# 4_-_EthernetPHY.net
KiCad netlist of a schematic drawn in Altium Designer
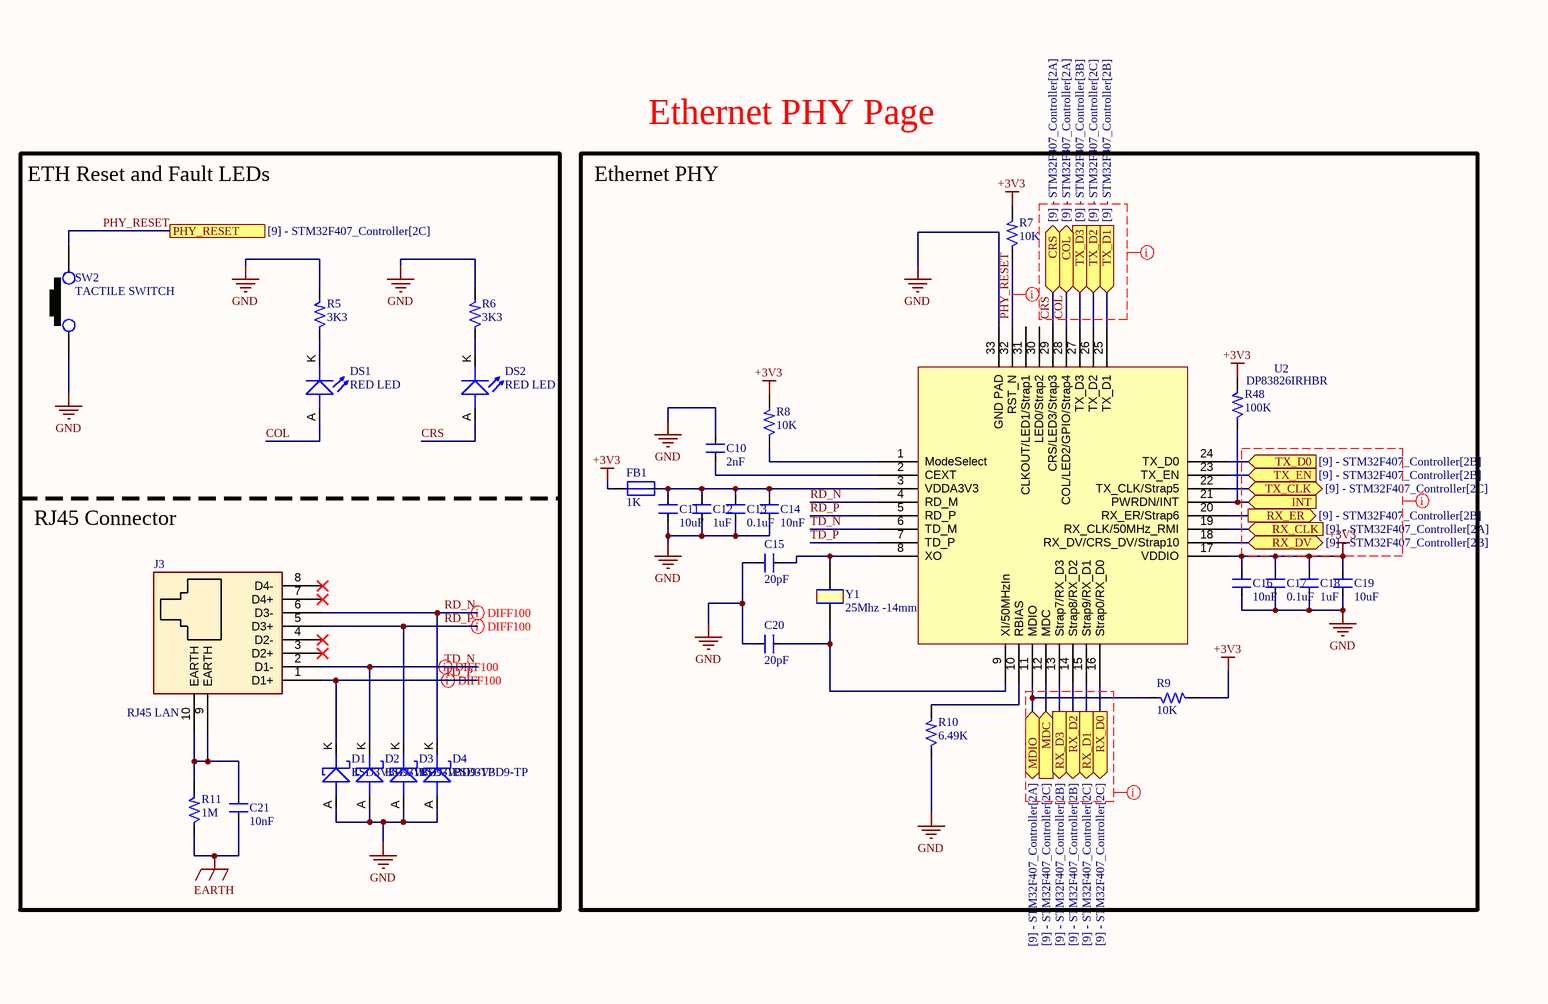
[diagram p0: [4] - EthernetPHY.SchDoc]

(export (version "E")
  (design (tool "Eeschema 10.0.6"))
  (components
    (comp (ref "C10")
      (value "2nF")
      (footprint "CAP_0805")
      (description "2000pF ±10% 50V Ceramic Capacitor X7R 0805 (2012 Metric)")
      (fields
        (field (name "MANUFACTURER") "Samsung Electro-Mechanics")
        (field (name "MANUFACTURER PART NUMBER") "CL21B202KBANNNC")
      )
      (libsource (lib "ESTEEMPCBLIB") (part "CAP_2nF-50V-10%-0805"))
    )
    (comp (ref "C11")
      (value "10uF")
      (footprint "CAP_1206")
      (description "10µF ±10% 50V Ceramic Capacitor X7R 1206 (3216 Metric)")
      (fields
        (field (name "MANUFACTURER") "KEMET")
        (field (name "MANUFACTURER PART NUMBER") "CL31B106KBHNNNE")
      )
      (libsource (lib "ESTEEMPCBLIB") (part "CAP_10uF-50V-10%-1206"))
    )
    (comp (ref "C12")
      (value "1uF")
      (footprint "CAP_0805")
      (description "1µF ±5% 50V Ceramic Capacitor X7R 0805 (2012 Metric)")
      (fields
        (field (name "MANUFACTURER") "Samsung")
        (field (name "MANUFACTURER PART NUMBER") "CC0805JKX7R9BB105")
      )
      (libsource (lib "ESTEEMPCBLIB") (part "CAP_1uF-50V-5%-0805"))
    )
    (comp (ref "C13")
      (value "0.1uF")
      (footprint "CAP_0805")
      (description "0.1µF ±5% 50V Ceramic Capacitor X7R 0805 (2012 Metric)")
      (fields
        (field (name "MANUFACTURER") "AVX Corporation")
        (field (name "MANUFACTURER PART NUMBER") "08055C104JAT4A")
      )
      (libsource (lib "ESTEEMPCBLIB") (part "CAP_0.1uF-50V-5%-0805"))
    )
    (comp (ref "C14")
      (value "10nF")
      (footprint "CAP_0805")
      (description "10000pF ±10% 50V Ceramic Capacitor X7R 0805 (2012 Metric)")
      (fields
        (field (name "MANUFACTURER") "Samsung")
        (field (name "MANUFACTURER PART NUMBER") "C0805C103K5RECAUTO")
      )
      (libsource (lib "ESTEEMPCBLIB") (part "CAP_10nF-50V-10%-0805"))
    )
    (comp (ref "C15")
      (value "20pF")
      (footprint "CAP_0805")
      (description "±10% 50V Ceramic Capacitor C0G, NP0 0805 (2012 Metric)")
      (fields
        (field (name "MANUFACTURER") "AVX Corporation")
        (field (name "MANUFACTURER PART NUMBER") "08055A200KAT2A")
      )
      (libsource (lib "ESTEEMPCBLIB") (part "CAP_20pF-50V-10%-0805"))
    )
    (comp (ref "C16")
      (value "10nF")
      (footprint "CAP_0805")
      (description "10000pF ±10% 50V Ceramic Capacitor X7R 0805 (2012 Metric)")
      (fields
        (field (name "MANUFACTURER") "Samsung")
        (field (name "MANUFACTURER PART NUMBER") "C0805C103K5RECAUTO")
      )
      (libsource (lib "ESTEEMPCBLIB") (part "CAP_10nF-50V-10%-0805"))
    )
    (comp (ref "C17")
      (value "0.1uF")
      (footprint "CAP_0805")
      (description "0.1µF ±5% 50V Ceramic Capacitor X7R 0805 (2012 Metric)")
      (fields
        (field (name "MANUFACTURER") "AVX Corporation")
        (field (name "MANUFACTURER PART NUMBER") "08055C104JAT4A")
      )
      (libsource (lib "ESTEEMPCBLIB") (part "CAP_0.1uF-50V-5%-0805"))
    )
    (comp (ref "C18")
      (value "1uF")
      (footprint "CAP_0805")
      (description "1µF ±5% 50V Ceramic Capacitor X7R 0805 (2012 Metric)")
      (fields
        (field (name "MANUFACTURER") "Samsung")
        (field (name "MANUFACTURER PART NUMBER") "CC0805JKX7R9BB105")
      )
      (libsource (lib "ESTEEMPCBLIB") (part "CAP_1uF-50V-5%-0805"))
    )
    (comp (ref "C19")
      (value "10uF")
      (footprint "CAP_1206")
      (description "10µF ±10% 50V Ceramic Capacitor X7R 1206 (3216 Metric)")
      (fields
        (field (name "MANUFACTURER") "KEMET")
        (field (name "MANUFACTURER PART NUMBER") "CL31B106KBHNNNE")
      )
      (libsource (lib "ESTEEMPCBLIB") (part "CAP_10uF-50V-10%-1206"))
    )
    (comp (ref "C20")
      (value "20pF")
      (footprint "CAP_0805")
      (description "±10% 50V Ceramic Capacitor C0G, NP0 0805 (2012 Metric)")
      (fields
        (field (name "MANUFACTURER") "AVX Corporation")
        (field (name "MANUFACTURER PART NUMBER") "08055A200KAT2A")
      )
      (libsource (lib "ESTEEMPCBLIB") (part "CAP_20pF-50V-10%-0805"))
    )
    (comp (ref "C21")
      (value "10nF")
      (footprint "CAP_P196_102X287_H332_RAD_TH")
      (description "10000pF ±10% 1000V (1kV) Ceramic Capacitor X7R Radial")
      (fields
        (field (name "MANUFACTURER") "Yageo")
        (field (name "MANUFACTURER PART NUMBER") "RDER73A103K2K1H03B")
      )
      (libsource (lib "ESTEEMPCBLIB") (part "CAP_10nF-1KV-10%-RAD-TH"))
    )
    (comp (ref "D1")
      (value "ESD3V3D9-TP")
      (footprint "DIO_SOD-923")
      (description "TVS DIODE 3.3V 8.8V SOD923")
      (fields (field (name "MANUFACTURER") "Micro Commercial Co"))
      (libsource (lib "ESTEEMPCBLIB") (part "DIO-T_3.3V-8.8V-10A-SOD923"))
    )
    (comp (ref "D2")
      (value "ESD3V3D9-TP")
      (footprint "DIO_SOD-923")
      (description "TVS DIODE 3.3V 8.8V SOD923")
      (fields (field (name "MANUFACTURER") "Micro Commercial Co"))
      (libsource (lib "ESTEEMPCBLIB") (part "DIO-T_3.3V-8.8V-10A-SOD923"))
    )
    (comp (ref "D3")
      (value "ESD3V3D9-TP")
      (footprint "DIO_SOD-923")
      (description "TVS DIODE 3.3V 8.8V SOD923")
      (fields (field (name "MANUFACTURER") "Micro Commercial Co"))
      (libsource (lib "ESTEEMPCBLIB") (part "DIO-T_3.3V-8.8V-10A-SOD923"))
    )
    (comp (ref "D4")
      (value "ESD3V3D9-TP")
      (footprint "DIO_SOD-923")
      (description "TVS DIODE 3.3V 8.8V SOD923")
      (fields (field (name "MANUFACTURER") "Micro Commercial Co"))
      (libsource (lib "ESTEEMPCBLIB") (part "DIO-T_3.3V-8.8V-10A-SOD923"))
    )
    (comp (ref "DS1")
      (value "RED LED")
      (footprint "LED_0805")
      (description "Red 631nm LED Indication - Discrete 2V 0805 (2012 Metric)")
      (fields
        (field (name "MANUFACTURER") "Vishay Lite-On")
        (field (name "MANUFACTURER PART NUMBER") "LTST-C171KRKT")
      )
      (libsource (lib "ESTEEMPCBLIB") (part "LED_RED-2V-20mA-0805"))
    )
    (comp (ref "DS2")
      (value "RED LED")
      (footprint "LED_0805")
      (description "Red 631nm LED Indication - Discrete 2V 0805 (2012 Metric)")
      (fields
        (field (name "MANUFACTURER") "Vishay Lite-On")
        (field (name "MANUFACTURER PART NUMBER") "LTST-C171KRKT")
      )
      (libsource (lib "ESTEEMPCBLIB") (part "LED_RED-2V-20mA-0805"))
    )
    (comp (ref "FB1")
      (value "1K")
      (footprint "IND_0805")
      (description "1 kOhms @ 100MHz 1 Power Line Ferrite Bead 0805 (2012 Metric) 1.6A")
      (fields
        (field (name "MANUFACTURER") "Laird")
        (field (name "MANUFACTURER PART NUMBER") "BLM21SP102SH1D")
      )
      (libsource (lib "ESTEEMPCBLIB") (part "FB_1K-100MHZ-1.6A-0805"))
    )
    (comp (ref "J3")
      (value "RJ45 LAN")
      (footprint "CON10_P106_RJ45_TH_ST")
      (description "8 Pins, 2 Row 2.54mm Pitch, right angle Connector, male")
      (fields
        (field (name "MANUFACTURER") "Assmann")
        (field (name "MANUFACTURER PART NUMBER") "A-2004-2-4-LPS-N-R")
      )
      (libsource (lib "ESTEEMPCBLIB") (part "CON-SKT-RJ_8C8P-RA-TH"))
    )
    (comp (ref "R5")
      (value "3K3")
      (footprint "RES_0603")
      (description "3.3 kOhms ±1% 0.1W, 1/10W Chip Resistor 0603 (1608 Metric) Automotive AEC-Q200 Thick Film")
      (fields (field (name "MANUFACTURER") "Wilson") (field (name "MANUFACTURER PART NUMBER") "WR06X3301FTL"))
      (libsource (lib "ESTEEMPCBLIB") (part "RES_3.3K-0.1W-1%-0603"))
    )
    (comp (ref "R6")
      (value "3K3")
      (footprint "RES_0603")
      (description "3.3 kOhms ±1% 0.1W, 1/10W Chip Resistor 0603 (1608 Metric) Automotive AEC-Q200 Thick Film")
      (fields (field (name "MANUFACTURER") "Wilson") (field (name "MANUFACTURER PART NUMBER") "WR06X3301FTL"))
      (libsource (lib "ESTEEMPCBLIB") (part "RES_3.3K-0.1W-1%-0603"))
    )
    (comp (ref "R7")
      (value "10K")
      (footprint "RES_0603")
      (description "10 kOhms ±1% 0.1W, 1/10W Chip Resistor 0603 (1608 Metric) Automotive AEC-Q200 Thick Film")
      (fields (field (name "MANUFACTURER") "Walsin") (field (name "MANUFACTURER PART NUMBER") "WR06X1002FTL"))
      (libsource (lib "ESTEEMPCBLIB") (part "RES_10K-0.1W-1%-0603"))
    )
    (comp (ref "R8")
      (value "10K")
      (footprint "RES_0603")
      (description "10 kOhms ±1% 0.1W, 1/10W Chip Resistor 0603 (1608 Metric) Automotive AEC-Q200 Thick Film")
      (fields (field (name "MANUFACTURER") "Walsin") (field (name "MANUFACTURER PART NUMBER") "WR06X1002FTL"))
      (libsource (lib "ESTEEMPCBLIB") (part "RES_10K-0.1W-1%-0603"))
    )
    (comp (ref "R9")
      (value "10K")
      (footprint "RES_0603")
      (description "10 kOhms ±1% 0.1W, 1/10W Chip Resistor 0603 (1608 Metric) Automotive AEC-Q200 Thick Film")
      (fields (field (name "MANUFACTURER") "Walsin") (field (name "MANUFACTURER PART NUMBER") "WR06X1002FTL"))
      (libsource (lib "ESTEEMPCBLIB") (part "RES_10K-0.1W-1%-0603"))
    )
    (comp (ref "R10")
      (value "6.49K")
      (footprint "RES_0805")
      (description "6.49 kOhms ±1% 0.125W, 1/8W Chip Resistor 0805 (2012 Metric) Moisture Resistant Thick Film")
      (fields
        (field (name "MANUFACTURER") "Stackpole Electronics")
        (field (name "MANUFACTURER PART NUMBER") "RC0805FR-076K49L")
      )
      (libsource (lib "ESTEEMPCBLIB") (part "RES_6.49K-0.125W-1%-0805"))
    )
    (comp (ref "R11")
      (value "1M")
      (footprint "RES_1206")
      (fields (field (name "MANUFACTURER") "Walsin") (field (name "MANUFACTURER PART NUMBER") "WR12X1004FTL"))
      (libsource (lib "ESTEEMPCBLIB") (part "RES_1M-0.25W-1%-1206"))
    )
    (comp (ref "R48")
      (value "100K")
      (footprint "RES_0603")
      (description "100 kOhms ±1% 0.1W, 1/10W Chip Resistor 0603 (1608 Metric) Automotive AEC-Q200 Thick Film")
      (fields
        (field (name "MANUFACTURER") "Stackpole Electronics")
        (field (name "MANUFACTURER PART NUMBER") "RMCF0603FT100K")
      )
      (libsource (lib "ESTEEMPCBLIB") (part "RES_100K-0.1W-1%-0603"))
    )
    (comp (ref "SW2")
      (value "TACTILE SWITCH")
      (footprint "SW_342_SMD")
      (description "Tactile Switch SPST-NO Top Actuated Surface Mount")
      (fields
        (field (name "MANUFACTURER") "ITT C&K")
        (field (name "MANUFACTURER PART NUMBER") "RS-282G05A3-SMRT")
      )
      (libsource (lib "ESTEEMPCBLIB") (part "SW1_RS-282G05A3-SMRT-SMD"))
    )
    (comp (ref "U2")
      (value "DP83826IRHBR")
      (footprint "VQFN32_19_218_23X9_SMD")
      (fields (field (name "MANUFACTURER") "Texas Instruments"))
      (libsource (lib "ESTEEMPCBLIB") (part "IC_DP83826IRHBR"))
    )
    (comp (ref "Y1")
      (value "25Mhz -14mm")
      (footprint "XTAL_314_240X47_SMD")
      (description "25MHz ±30ppm Crystal 20pF 30 Ohms HC-49/US")
      (fields
        (field (name "MANUFACTURER") "Abracon")
        (field (name "MANUFACTURER PART NUMBER") "FOXSDLF/250F-20")
      )
      (libsource (lib "ESTEEMPCBLIB") (part "XTAL_25Mhz-FOXSDLF/250F-20"))
    )
  )
  (nets
    (net (code "1") (name "+3V3") (class "Default")
      (node (ref "C16") (pin "1") (pinfunction "1_1") (pintype "passive"))
      (node (ref "C17") (pin "2") (pinfunction "2_2") (pintype "passive"))
      (node (ref "C18") (pin "1") (pinfunction "1_1") (pintype "passive"))
      (node (ref "C19") (pin "2") (pinfunction "2_2") (pintype "passive"))
      (node (ref "FB1") (pin "1") (pinfunction "1_1") (pintype "passive"))
      (node (ref "R48") (pin "2") (pinfunction "2_2") (pintype "passive"))
      (node (ref "R7") (pin "2") (pinfunction "2_2") (pintype "passive"))
      (node (ref "R8") (pin "2") (pinfunction "2_2") (pintype "passive"))
      (node (ref "R9") (pin "2") (pinfunction "2_2") (pintype "passive"))
      (node (ref "U2") (pin "17") (pinfunction "VDDIO_17") (pintype "passive"))
    )
    (net (code "2") (name "/COL") (class "Default")
      (node (ref "DS1") (pin "A") (pinfunction "ANODE_A") (pintype "passive"))
      (node (ref "U2") (pin "28") (pinfunction "COL/LED2/GPIO/Strap4_28") (pintype "passive"))
    )
    (net (code "3") (name "/CRS") (class "Default")
      (node (ref "DS2") (pin "A") (pinfunction "ANODE_A") (pintype "passive"))
      (node (ref "U2") (pin "29") (pinfunction "CRS/LED3/Strap3_29") (pintype "passive"))
    )
    (net (code "4") (name "/INT") (class "Default")
      (node (ref "R48") (pin "1") (pinfunction "1_1") (pintype "passive"))
      (node (ref "U2") (pin "21") (pinfunction "PWRDN/INT_21") (pintype "passive"))
    )
    (net (code "5") (name "/MDC") (class "Default")
      (node (ref "U2") (pin "12") (pinfunction "MDC_12") (pintype "passive"))
    )
    (net (code "6") (name "/MDIO") (class "Default")
      (node (ref "R9") (pin "1") (pinfunction "1_1") (pintype "passive"))
      (node (ref "U2") (pin "11") (pinfunction "MDIO_11") (pintype "passive"))
    )
    (net (code "7") (name "/PHY_RESET") (class "Default")
      (node (ref "R7") (pin "1") (pinfunction "1_1") (pintype "passive"))
      (node (ref "SW2") (pin "2") (pinfunction "2_2") (pintype "passive"))
      (node (ref "U2") (pin "32") (pinfunction "RST_N_32") (pintype "passive"))
    )
    (net (code "8") (name "/RD_N") (class "Default")
      (node (ref "D4") (pin "K") (pinfunction "K_K") (pintype "passive"))
      (node (ref "J3") (pin "6") (pinfunction "D3-_6") (pintype "passive"))
      (node (ref "U2") (pin "4") (pinfunction "RD_M_4") (pintype "passive"))
    )
    (net (code "9") (name "/RD_P") (class "Default")
      (node (ref "D3") (pin "K") (pinfunction "K_K") (pintype "passive"))
      (node (ref "J3") (pin "5") (pinfunction "D3+_5") (pintype "passive"))
      (node (ref "U2") (pin "5") (pinfunction "RD_P_5") (pintype "passive"))
    )
    (net (code "10") (name "/RX_CLK") (class "Default")
      (node (ref "U2") (pin "19") (pinfunction "RX_CLK/50MHz_RMI_19") (pintype "passive"))
    )
    (net (code "11") (name "/RX_D0") (class "Default")
      (node (ref "U2") (pin "16") (pinfunction "Strap0/RX_D0_16") (pintype "passive"))
    )
    (net (code "12") (name "/RX_D1") (class "Default")
      (node (ref "U2") (pin "15") (pinfunction "Strap9/RX_D1_15") (pintype "passive"))
    )
    (net (code "13") (name "/RX_D2") (class "Default")
      (node (ref "U2") (pin "14") (pinfunction "Strap8/RX_D2_14") (pintype "passive"))
    )
    (net (code "14") (name "/RX_D3") (class "Default")
      (node (ref "U2") (pin "13") (pinfunction "Strap7/RX_D3_13") (pintype "passive"))
    )
    (net (code "15") (name "/RX_DV") (class "Default")
      (node (ref "U2") (pin "18") (pinfunction "RX_DV/CRS_DV/Strap10_18") (pintype "passive"))
    )
    (net (code "16") (name "/RX_ER") (class "Default")
      (node (ref "U2") (pin "20") (pinfunction "RX_ER/Strap6_20") (pintype "passive"))
    )
    (net (code "17") (name "/TD_N") (class "Default")
      (node (ref "D2") (pin "K") (pinfunction "K_K") (pintype "passive"))
      (node (ref "J3") (pin "2") (pinfunction "D1-_2") (pintype "passive"))
      (node (ref "U2") (pin "6") (pinfunction "TD_M_6") (pintype "passive"))
    )
    (net (code "18") (name "/TD_P") (class "Default")
      (node (ref "D1") (pin "K") (pinfunction "K_K") (pintype "passive"))
      (node (ref "J3") (pin "1") (pinfunction "D1+_1") (pintype "passive"))
      (node (ref "U2") (pin "7") (pinfunction "TD_P_7") (pintype "passive"))
    )
    (net (code "19") (name "/TX_CLK") (class "Default")
      (node (ref "U2") (pin "22") (pinfunction "TX_CLK/Strap5_22") (pintype "passive"))
    )
    (net (code "20") (name "/TX_D0") (class "Default")
      (node (ref "U2") (pin "24") (pinfunction "TX_D0_24") (pintype "passive"))
    )
    (net (code "21") (name "/TX_D1") (class "Default")
      (node (ref "U2") (pin "25") (pinfunction "TX_D1_25") (pintype "passive"))
    )
    (net (code "22") (name "/TX_D2") (class "Default")
      (node (ref "U2") (pin "26") (pinfunction "TX_D2_26") (pintype "passive"))
    )
    (net (code "23") (name "/TX_D3") (class "Default")
      (node (ref "U2") (pin "27") (pinfunction "TX_D3_27") (pintype "passive"))
    )
    (net (code "24") (name "/TX_EN") (class "Default")
      (node (ref "U2") (pin "23") (pinfunction "TX_EN_23") (pintype "passive"))
    )
    (net (code "25") (name "EARTH") (class "Default")
      (node (ref "C21") (pin "1") (pinfunction "1_1") (pintype "passive"))
      (node (ref "R11") (pin "1") (pinfunction "1_1") (pintype "passive"))
    )
    (net (code "26") (name "GND") (class "Default")
      (node (ref "C10") (pin "1") (pinfunction "1_1") (pintype "passive"))
      (node (ref "C11") (pin "1") (pinfunction "1_1") (pintype "passive"))
      (node (ref "C12") (pin "1") (pinfunction "1_1") (pintype "passive"))
      (node (ref "C13") (pin "2") (pinfunction "2_2") (pintype "passive"))
      (node (ref "C14") (pin "1") (pinfunction "1_1") (pintype "passive"))
      (node (ref "C15") (pin "1") (pinfunction "1_1") (pintype "passive"))
      (node (ref "C16") (pin "2") (pinfunction "2_2") (pintype "passive"))
      (node (ref "C17") (pin "1") (pinfunction "1_1") (pintype "passive"))
      (node (ref "C18") (pin "2") (pinfunction "2_2") (pintype "passive"))
      (node (ref "C19") (pin "1") (pinfunction "1_1") (pintype "passive"))
      (node (ref "C20") (pin "1") (pinfunction "1_1") (pintype "passive"))
      (node (ref "D1") (pin "A") (pinfunction "A_A") (pintype "passive"))
      (node (ref "D2") (pin "A") (pinfunction "A_A") (pintype "passive"))
      (node (ref "D3") (pin "A") (pinfunction "A_A") (pintype "passive"))
      (node (ref "D4") (pin "A") (pinfunction "A_A") (pintype "passive"))
      (node (ref "R10") (pin "1") (pinfunction "1_1") (pintype "passive"))
      (node (ref "R5") (pin "2") (pinfunction "2_2") (pintype "passive"))
      (node (ref "R6") (pin "2") (pinfunction "2_2") (pintype "passive"))
      (node (ref "SW2") (pin "1") (pinfunction "1_1") (pintype "passive"))
      (node (ref "U2") (pin "33") (pinfunction "GND_PAD_33") (pintype "passive"))
    )
    (net (code "27") (name "Net-(C21-Pad2)") (class "Default")
      (node (ref "C21") (pin "2") (pinfunction "2_2") (pintype "passive"))
      (node (ref "J3") (pin "10") (pinfunction "EARTH_10") (pintype "passive"))
      (node (ref "J3") (pin "9") (pinfunction "EARTH_9") (pintype "passive"))
      (node (ref "R11") (pin "2") (pinfunction "2_2") (pintype "passive"))
    )
    (net (code "28") (name "Net-(DS1-CATHODE)") (class "Default")
      (node (ref "DS1") (pin "K") (pinfunction "CATHODE_K") (pintype "passive"))
      (node (ref "R5") (pin "1") (pinfunction "1_1") (pintype "passive"))
    )
    (net (code "29") (name "Net-(DS2-CATHODE)") (class "Default")
      (node (ref "DS2") (pin "K") (pinfunction "CATHODE_K") (pintype "passive"))
      (node (ref "R6") (pin "1") (pinfunction "1_1") (pintype "passive"))
    )
    (net (code "30") (name "Net-(U2-CEXT)") (class "Default")
      (node (ref "C10") (pin "2") (pinfunction "2_2") (pintype "passive"))
      (node (ref "U2") (pin "2") (pinfunction "CEXT_2") (pintype "passive"))
    )
    (net (code "31") (name "Net-(U2-ModeSelect)") (class "Default")
      (node (ref "R8") (pin "1") (pinfunction "1_1") (pintype "passive"))
      (node (ref "U2") (pin "1") (pinfunction "ModeSelect_1") (pintype "passive"))
    )
    (net (code "32") (name "Net-(U2-RBIAS)") (class "Default")
      (node (ref "R10") (pin "2") (pinfunction "2_2") (pintype "passive"))
      (node (ref "U2") (pin "10") (pinfunction "RBIAS_10") (pintype "passive"))
    )
    (net (code "33") (name "Net-(U2-VDDA3V3)") (class "Default")
      (node (ref "C11") (pin "2") (pinfunction "2_2") (pintype "passive"))
      (node (ref "C12") (pin "2") (pinfunction "2_2") (pintype "passive"))
      (node (ref "C13") (pin "1") (pinfunction "1_1") (pintype "passive"))
      (node (ref "C14") (pin "2") (pinfunction "2_2") (pintype "passive"))
      (node (ref "FB1") (pin "2") (pinfunction "2_2") (pintype "passive"))
      (node (ref "U2") (pin "3") (pinfunction "VDDA3V3_3") (pintype "passive"))
    )
    (net (code "34") (name "Net-(U2-XI{slash}50MHzIn)") (class "Default")
      (node (ref "C20") (pin "2") (pinfunction "2_2") (pintype "passive"))
      (node (ref "U2") (pin "9") (pinfunction "XI/50MHzIn_9") (pintype "passive"))
      (node (ref "Y1") (pin "1") (pinfunction "1_1") (pintype "passive"))
    )
    (net (code "35") (name "Net-(U2-XO)") (class "Default")
      (node (ref "C15") (pin "2") (pinfunction "2_2") (pintype "passive"))
      (node (ref "U2") (pin "8") (pinfunction "XO_8") (pintype "passive"))
      (node (ref "Y1") (pin "2") (pinfunction "2_2") (pintype "passive"))
    )
    (net (code "36") (name "unconnected-(J3-D2+-Pad3)") (class "Default")
      (node (ref "J3") (pin "3") (pinfunction "D2+_3") (pintype "passive+no_connect"))
    )
    (net (code "37") (name "unconnected-(J3-D2--Pad4)") (class "Default")
      (node (ref "J3") (pin "4") (pinfunction "D2-_4") (pintype "passive+no_connect"))
    )
    (net (code "38") (name "unconnected-(J3-D4+-Pad7)") (class "Default")
      (node (ref "J3") (pin "7") (pinfunction "D4+_7") (pintype "passive+no_connect"))
    )
    (net (code "39") (name "unconnected-(J3-D4--Pad8)") (class "Default")
      (node (ref "J3") (pin "8") (pinfunction "D4-_8") (pintype "passive+no_connect"))
    )
    (net (code "40") (name "unconnected-(U2-CLKOUT{slash}LED1{slash}Strap1-Pad31)") (class "Default")
      (node (ref "U2") (pin "31") (pinfunction "CLKOUT/LED1/Strap1_31") (pintype "passive"))
    )
    (net (code "41") (name "unconnected-(U2-LED0{slash}Strap2-Pad30)") (class "Default")
      (node (ref "U2") (pin "30") (pinfunction "LED0/Strap2_30") (pintype "passive"))
    )
  )
)
